# SH12_-_RGMII_Ethernet.net
KiCad netlist of a schematic drawn in Altium Designer
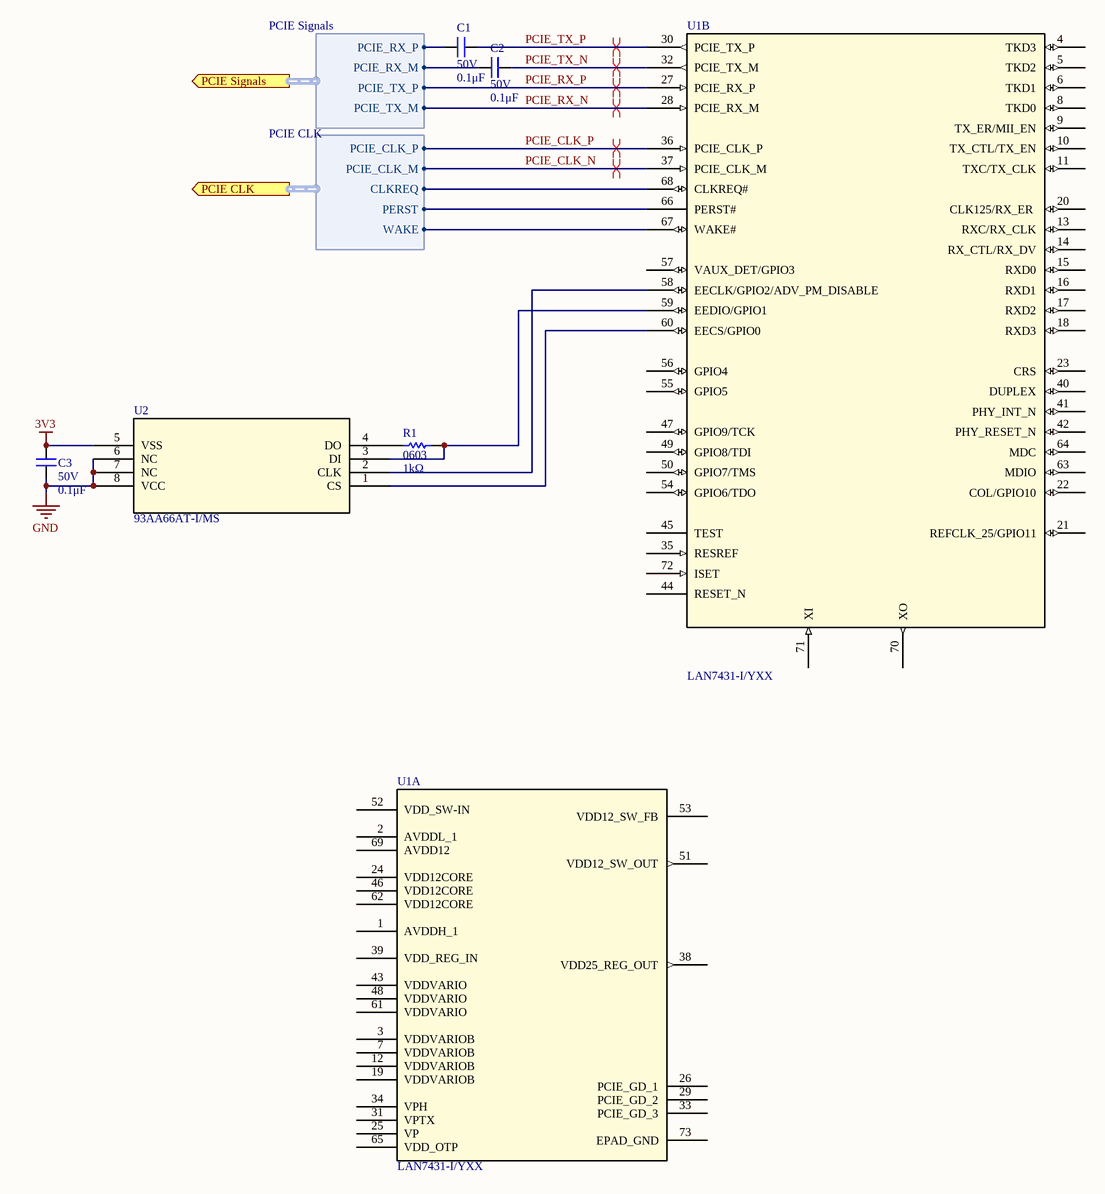
[diagram p0: SH12 - RGMII Ethernet.SchDoc]

(export (version "E")
  (design (tool "Eeschema 10.0.6"))
  (components
    (comp (ref "C1")
      (value "0.1μF")
      (footprint "CAP0603")
      (description "CAP CER 0.1UF 50V X7R 0603")
      (fields (field (name "VOLTAGE RATING") "50V") (field (name "Comment") "CAP_0.1uF_50V_0603"))
      (libsource (lib "UWRT_Schematic_Library_2020") (part "CAP_0.1uF_50V_0603"))
    )
    (comp (ref "C2")
      (value "0.1μF")
      (footprint "CAP0603")
      (description "CAP CER 0.1UF 50V X7R 0603")
      (fields (field (name "VOLTAGE RATING") "50V") (field (name "Comment") "CAP_0.1uF_50V_0603"))
      (libsource (lib "UWRT_Schematic_Library_2020") (part "CAP_0.1uF_50V_0603"))
    )
    (comp (ref "C3")
      (value "0.1μF")
      (footprint "CAP0603")
      (description "CAP CER 0.1UF 50V X7R 0603")
      (fields (field (name "VOLTAGE RATING") "50V") (field (name "Comment") "CAP_0.1uF_50V_0603"))
      (libsource (lib "UWRT_Schematic_Library_2020") (part "CAP_0.1uF_50V_0603"))
    )
    (comp (ref "R1")
      (value "1kΩ")
      (footprint "RES0603")
      (description "RES 1K OHM 5% 1/10W 0603")
      (fields (field (name "PACKAGE/FOOTPRINT") "0603") (field (name "Comment") "RES_1kΩ_0603_5%"))
      (libsource (lib "UWRT_Schematic_Library_2020") (part "RES_1kΩ_0603_5%"))
    )
    (comp (ref "U1")
      (value "LAN7431-I/YXX")
      (description "Serial I/O Controller, 4 Channel(s), 256MBps, CMOS")
      (fields (field (name "MANUFACTURER") "Microchip"))
      (libsource (lib "UWRT_Schematic_Library_2020") (part "LAN7431-I/YXX"))
    )
    (comp (ref "U2")
      (value "93AA66AT-I/MS")
      (footprint "MSOP8_MC_MCH")
      (description "No Description Available")
      (fields (field (name "COPYRIGHT") "Copyright (C) 2018 Accelerated Designs. All rights reserved"))
      (libsource (lib "UWRT_Schematic_Library_2020") (part "93AA66AT-I/MS"))
    )
  )
  (nets
    (net (code "4") (name "/CLKREQ") (class "Default")
      (node (ref "U1") (pin "68") (pinfunction "CLKREQ#_68") (pintype "bidirectional"))
    )
    (net (code "5") (name "/PCIE_CLK_N") (class "Default")
      (node (ref "U1") (pin "37") (pinfunction "PCIE_CLK_M_37") (pintype "input"))
    )
    (net (code "6") (name "/PCIE_CLK_P") (class "Default")
      (node (ref "U1") (pin "36") (pinfunction "PCIE_CLK_P_36") (pintype "input"))
    )
    (net (code "7") (name "/PCIE_RX_M") (class "Default")
      (node (ref "C2") (pin "1") (pinfunction "1_1") (pintype "passive"))
    )
    (net (code "8") (name "/PCIE_RX_N") (class "Default")
      (node (ref "U1") (pin "28") (pinfunction "PCIE_RX_M_28") (pintype "input"))
    )
    (net (code "9") (name "/PCIE_RX_P") (class "Default")
      (node (ref "U1") (pin "27") (pinfunction "PCIE_RX_P_27") (pintype "input"))
    )
    (net (code "10") (name "/PCIE_TX_N") (class "Default")
      (node (ref "C2") (pin "2") (pinfunction "2_2") (pintype "passive"))
      (node (ref "U1") (pin "32") (pinfunction "PCIE_TX_M_32") (pintype "output"))
    )
    (net (code "11") (name "/PCIE_TX_P") (class "Default")
      (node (ref "C1") (pin "2") (pinfunction "2_2") (pintype "passive"))
      (node (ref "U1") (pin "30") (pinfunction "PCIE_TX_P_30") (pintype "output"))
    )
    (net (code "12") (name "/PERST") (class "Default")
      (node (ref "U1") (pin "66") (pinfunction "PERST#_66") (pintype "passive"))
    )
    (net (code "13") (name "/WAKE") (class "Default")
      (node (ref "U1") (pin "67") (pinfunction "WAKE#_67") (pintype "bidirectional"))
    )
    (net (code "16") (name "3V3") (class "Default")
      (node (ref "C3") (pin "2") (pinfunction "2_2") (pintype "passive"))
      (node (ref "U2") (pin "5") (pinfunction "VSS_5") (pintype "passive"))
    )
    (net (code "17") (name "GND") (class "Default")
      (node (ref "C3") (pin "1") (pinfunction "1_1") (pintype "passive"))
      (node (ref "U2") (pin "6") (pinfunction "NC_6") (pintype "passive"))
      (node (ref "U2") (pin "7") (pinfunction "NC_7") (pintype "passive"))
      (node (ref "U2") (pin "8") (pinfunction "VCC_8") (pintype "passive"))
    )
    (net (code "18") (name "Net-(U1B-EECLK{slash}GPIO2{slash}ADV_PM_DISABLE)") (class "Default")
      (node (ref "U1") (pin "58") (pinfunction "EECLK/GPIO2/ADV_PM_DISABLE_58") (pintype "bidirectional"))
      (node (ref "U2") (pin "2") (pinfunction "CLK_2") (pintype "passive"))
    )
    (net (code "19") (name "Net-(U1B-EECS{slash}GPIO0)") (class "Default")
      (node (ref "U1") (pin "60") (pinfunction "EECS/GPIO0_60") (pintype "bidirectional"))
      (node (ref "U2") (pin "1") (pinfunction "CS_1") (pintype "passive"))
    )
    (net (code "20") (name "Net-(U1B-EEDIO{slash}GPIO1)") (class "Default")
      (node (ref "R1") (pin "2") (pinfunction "2_2") (pintype "passive"))
      (node (ref "U1") (pin "59") (pinfunction "EEDIO/GPIO1_59") (pintype "bidirectional"))
      (node (ref "U2") (pin "3") (pinfunction "DI_3") (pintype "passive"))
    )
    (net (code "21") (name "Net-(U2-DO)") (class "Default")
      (node (ref "R1") (pin "1") (pinfunction "1_1") (pintype "passive"))
      (node (ref "U2") (pin "4") (pinfunction "DO_4") (pintype "passive"))
    )
    (net (code "22") (name "unconnected-(C1-Pad1)") (class "Default")
      (node (ref "C1") (pin "1") (pinfunction "1_1") (pintype "passive"))
    )
    (net (code "23") (name "unconnected-(U1A-AVDD12-Pad69)") (class "Default")
      (node (ref "U1") (pin "69") (pinfunction "AVDD12_69") (pintype "power_in"))
    )
    (net (code "24") (name "unconnected-(U1A-AVDDH_1-Pad1)") (class "Default")
      (node (ref "U1") (pin "1") (pinfunction "AVDDH_1_1") (pintype "power_in"))
    )
    (net (code "25") (name "unconnected-(U1A-AVDDL_1-Pad2)") (class "Default")
      (node (ref "U1") (pin "2") (pinfunction "AVDDL_1_2") (pintype "power_in"))
    )
    (net (code "26") (name "unconnected-(U1A-EPAD_GND-Pad73)") (class "Default")
      (node (ref "U1") (pin "73") (pinfunction "EPAD_GND_73") (pintype "passive"))
    )
    (net (code "27") (name "unconnected-(U1A-PCIE_GD_1-Pad26)") (class "Default")
      (node (ref "U1") (pin "26") (pinfunction "PCIE_GD_1_26") (pintype "power_in"))
    )
    (net (code "28") (name "unconnected-(U1A-PCIE_GD_2-Pad29)") (class "Default")
      (node (ref "U1") (pin "29") (pinfunction "PCIE_GD_2_29") (pintype "power_in"))
    )
    (net (code "29") (name "unconnected-(U1A-PCIE_GD_3-Pad33)") (class "Default")
      (node (ref "U1") (pin "33") (pinfunction "PCIE_GD_3_33") (pintype "power_in"))
    )
    (net (code "30") (name "unconnected-(U1A-VDD12CORE-Pad24)") (class "Default")
      (node (ref "U1") (pin "24") (pinfunction "VDD12CORE_24") (pintype "power_in"))
    )
    (net (code "31") (name "unconnected-(U1A-VDD12CORE-Pad46)") (class "Default")
      (node (ref "U1") (pin "46") (pinfunction "VDD12CORE_46") (pintype "power_in"))
    )
    (net (code "32") (name "unconnected-(U1A-VDD12CORE-Pad62)") (class "Default")
      (node (ref "U1") (pin "62") (pinfunction "VDD12CORE_62") (pintype "power_in"))
    )
    (net (code "33") (name "unconnected-(U1A-VDD12_SW_FB-Pad53)") (class "Default")
      (node (ref "U1") (pin "53") (pinfunction "VDD12_SW_FB_53") (pintype "power_in"))
    )
    (net (code "34") (name "unconnected-(U1A-VDD12_SW_OUT-Pad51)") (class "Default")
      (node (ref "U1") (pin "51") (pinfunction "VDD12_SW_OUT_51") (pintype "output"))
    )
    (net (code "35") (name "unconnected-(U1A-VDD25_REG_OUT-Pad38)") (class "Default")
      (node (ref "U1") (pin "38") (pinfunction "VDD25_REG_OUT_38") (pintype "output"))
    )
    (net (code "36") (name "unconnected-(U1A-VDDVARIO-Pad43)") (class "Default")
      (node (ref "U1") (pin "43") (pinfunction "VDDVARIO_43") (pintype "power_in"))
    )
    (net (code "37") (name "unconnected-(U1A-VDDVARIO-Pad48)") (class "Default")
      (node (ref "U1") (pin "48") (pinfunction "VDDVARIO_48") (pintype "power_in"))
    )
    (net (code "38") (name "unconnected-(U1A-VDDVARIO-Pad61)") (class "Default")
      (node (ref "U1") (pin "61") (pinfunction "VDDVARIO_61") (pintype "power_in"))
    )
    (net (code "39") (name "unconnected-(U1A-VDDVARIOB-Pad3)") (class "Default")
      (node (ref "U1") (pin "3") (pinfunction "VDDVARIOB_3") (pintype "power_in"))
    )
    (net (code "40") (name "unconnected-(U1A-VDDVARIOB-Pad7)") (class "Default")
      (node (ref "U1") (pin "7") (pinfunction "VDDVARIOB_7") (pintype "power_in"))
    )
    (net (code "41") (name "unconnected-(U1A-VDDVARIOB-Pad12)") (class "Default")
      (node (ref "U1") (pin "12") (pinfunction "VDDVARIOB_12") (pintype "power_in"))
    )
    (net (code "42") (name "unconnected-(U1A-VDDVARIOB-Pad19)") (class "Default")
      (node (ref "U1") (pin "19") (pinfunction "VDDVARIOB_19") (pintype "power_in"))
    )
    (net (code "43") (name "unconnected-(U1A-VDD_OTP-Pad65)") (class "Default")
      (node (ref "U1") (pin "65") (pinfunction "VDD_OTP_65") (pintype "power_in"))
    )
    (net (code "44") (name "unconnected-(U1A-VDD_REG_IN-Pad39)") (class "Default")
      (node (ref "U1") (pin "39") (pinfunction "VDD_REG_IN_39") (pintype "power_in"))
    )
    (net (code "45") (name "unconnected-(U1A-VDD_SW-IN-Pad52)") (class "Default")
      (node (ref "U1") (pin "52") (pinfunction "VDD_SW-IN_52") (pintype "power_in"))
    )
    (net (code "46") (name "unconnected-(U1A-VP-Pad25)") (class "Default")
      (node (ref "U1") (pin "25") (pinfunction "VP_25") (pintype "power_in"))
    )
    (net (code "47") (name "unconnected-(U1A-VPH-Pad34)") (class "Default")
      (node (ref "U1") (pin "34") (pinfunction "VPH_34") (pintype "power_in"))
    )
    (net (code "48") (name "unconnected-(U1A-VPTX-Pad31)") (class "Default")
      (node (ref "U1") (pin "31") (pinfunction "VPTX_31") (pintype "power_in"))
    )
    (net (code "49") (name "unconnected-(U1B-CLK125{slash}RX_ER-Pad20)") (class "Default")
      (node (ref "U1") (pin "20") (pinfunction "CLK125/RX_ER_20") (pintype "bidirectional"))
    )
    (net (code "50") (name "unconnected-(U1B-COL{slash}GPIO10-Pad22)") (class "Default")
      (node (ref "U1") (pin "22") (pinfunction "COL/GPIO10_22") (pintype "bidirectional"))
    )
    (net (code "51") (name "unconnected-(U1B-CRS-Pad23)") (class "Default")
      (node (ref "U1") (pin "23") (pinfunction "CRS_23") (pintype "bidirectional"))
    )
    (net (code "52") (name "unconnected-(U1B-DUPLEX-Pad40)") (class "Default")
      (node (ref "U1") (pin "40") (pinfunction "DUPLEX_40") (pintype "bidirectional"))
    )
    (net (code "53") (name "unconnected-(U1B-GPIO4-Pad56)") (class "Default")
      (node (ref "U1") (pin "56") (pinfunction "GPIO4_56") (pintype "bidirectional"))
    )
    (net (code "54") (name "unconnected-(U1B-GPIO5-Pad55)") (class "Default")
      (node (ref "U1") (pin "55") (pinfunction "GPIO5_55") (pintype "bidirectional"))
    )
    (net (code "55") (name "unconnected-(U1B-GPIO6{slash}TDO-Pad54)") (class "Default")
      (node (ref "U1") (pin "54") (pinfunction "GPIO6/TDO_54") (pintype "bidirectional"))
    )
    (net (code "56") (name "unconnected-(U1B-GPIO7{slash}TMS-Pad50)") (class "Default")
      (node (ref "U1") (pin "50") (pinfunction "GPIO7/TMS_50") (pintype "bidirectional"))
    )
    (net (code "57") (name "unconnected-(U1B-GPIO8{slash}TDI-Pad49)") (class "Default")
      (node (ref "U1") (pin "49") (pinfunction "GPIO8/TDI_49") (pintype "bidirectional"))
    )
    (net (code "58") (name "unconnected-(U1B-GPIO9{slash}TCK-Pad47)") (class "Default")
      (node (ref "U1") (pin "47") (pinfunction "GPIO9/TCK_47") (pintype "bidirectional"))
    )
    (net (code "59") (name "unconnected-(U1B-ISET-Pad72)") (class "Default")
      (node (ref "U1") (pin "72") (pinfunction "ISET_72") (pintype "input"))
    )
    (net (code "60") (name "unconnected-(U1B-MDC-Pad64)") (class "Default")
      (node (ref "U1") (pin "64") (pinfunction "MDC_64") (pintype "bidirectional"))
    )
    (net (code "61") (name "unconnected-(U1B-MDIO-Pad63)") (class "Default")
      (node (ref "U1") (pin "63") (pinfunction "MDIO_63") (pintype "bidirectional"))
    )
    (net (code "62") (name "unconnected-(U1B-PHY_INT_N-Pad41)") (class "Default")
      (node (ref "U1") (pin "41") (pinfunction "PHY_INT_N_41") (pintype "bidirectional"))
    )
    (net (code "63") (name "unconnected-(U1B-PHY_RESET_N-Pad42)") (class "Default")
      (node (ref "U1") (pin "42") (pinfunction "PHY_RESET_N_42") (pintype "bidirectional"))
    )
    (net (code "64") (name "unconnected-(U1B-REFCLK_25{slash}GPIO11-Pad21)") (class "Default")
      (node (ref "U1") (pin "21") (pinfunction "REFCLK_25/GPIO11_21") (pintype "bidirectional"))
    )
    (net (code "65") (name "unconnected-(U1B-RESET_N-Pad44)") (class "Default")
      (node (ref "U1") (pin "44") (pinfunction "RESET_N_44") (pintype "passive"))
    )
    (net (code "66") (name "unconnected-(U1B-RESREF-Pad35)") (class "Default")
      (node (ref "U1") (pin "35") (pinfunction "RESREF_35") (pintype "input"))
    )
    (net (code "67") (name "unconnected-(U1B-RXC{slash}RX_CLK-Pad13)") (class "Default")
      (node (ref "U1") (pin "13") (pinfunction "RXC/RX_CLK_13") (pintype "bidirectional"))
    )
    (net (code "68") (name "unconnected-(U1B-RXD0-Pad15)") (class "Default")
      (node (ref "U1") (pin "15") (pinfunction "RXD0_15") (pintype "bidirectional"))
    )
    (net (code "69") (name "unconnected-(U1B-RXD1-Pad16)") (class "Default")
      (node (ref "U1") (pin "16") (pinfunction "RXD1_16") (pintype "bidirectional"))
    )
    (net (code "70") (name "unconnected-(U1B-RXD2-Pad17)") (class "Default")
      (node (ref "U1") (pin "17") (pinfunction "RXD2_17") (pintype "bidirectional"))
    )
    (net (code "71") (name "unconnected-(U1B-RXD3-Pad18)") (class "Default")
      (node (ref "U1") (pin "18") (pinfunction "RXD3_18") (pintype "bidirectional"))
    )
    (net (code "72") (name "unconnected-(U1B-RX_CTL{slash}RX_DV-Pad14)") (class "Default")
      (node (ref "U1") (pin "14") (pinfunction "RX_CTL/RX_DV_14") (pintype "bidirectional"))
    )
    (net (code "73") (name "unconnected-(U1B-TEST-Pad45)") (class "Default")
      (node (ref "U1") (pin "45") (pinfunction "TEST_45") (pintype "passive"))
    )
    (net (code "74") (name "unconnected-(U1B-TKD0-Pad8)") (class "Default")
      (node (ref "U1") (pin "8") (pinfunction "TKD0_8") (pintype "bidirectional"))
    )
    (net (code "75") (name "unconnected-(U1B-TKD1-Pad6)") (class "Default")
      (node (ref "U1") (pin "6") (pinfunction "TKD1_6") (pintype "bidirectional"))
    )
    (net (code "76") (name "unconnected-(U1B-TKD2-Pad5)") (class "Default")
      (node (ref "U1") (pin "5") (pinfunction "TKD2_5") (pintype "bidirectional"))
    )
    (net (code "77") (name "unconnected-(U1B-TKD3-Pad4)") (class "Default")
      (node (ref "U1") (pin "4") (pinfunction "TKD3_4") (pintype "bidirectional"))
    )
    (net (code "78") (name "unconnected-(U1B-TXC{slash}TX_CLK-Pad11)") (class "Default")
      (node (ref "U1") (pin "11") (pinfunction "TXC/TX_CLK_11") (pintype "bidirectional"))
    )
    (net (code "79") (name "unconnected-(U1B-TX_CTL{slash}TX_EN-Pad10)") (class "Default")
      (node (ref "U1") (pin "10") (pinfunction "TX_CTL/TX_EN_10") (pintype "bidirectional"))
    )
    (net (code "80") (name "unconnected-(U1B-TX_ER{slash}MII_EN-Pad9)") (class "Default")
      (node (ref "U1") (pin "9") (pinfunction "TX_ER/MII_EN_9") (pintype "bidirectional"))
    )
    (net (code "81") (name "unconnected-(U1B-VAUX_DET{slash}GPIO3-Pad57)") (class "Default")
      (node (ref "U1") (pin "57") (pinfunction "VAUX_DET/GPIO3_57") (pintype "bidirectional"))
    )
    (net (code "82") (name "unconnected-(U1B-XI-Pad71)") (class "Default")
      (node (ref "U1") (pin "71") (pinfunction "XI_71") (pintype "input"))
    )
    (net (code "83") (name "unconnected-(U1B-XO-Pad70)") (class "Default")
      (node (ref "U1") (pin "70") (pinfunction "XO_70") (pintype "output"))
    )
  )
)
